# Sheet3.net
KiCad netlist of a schematic drawn in Altium Designer
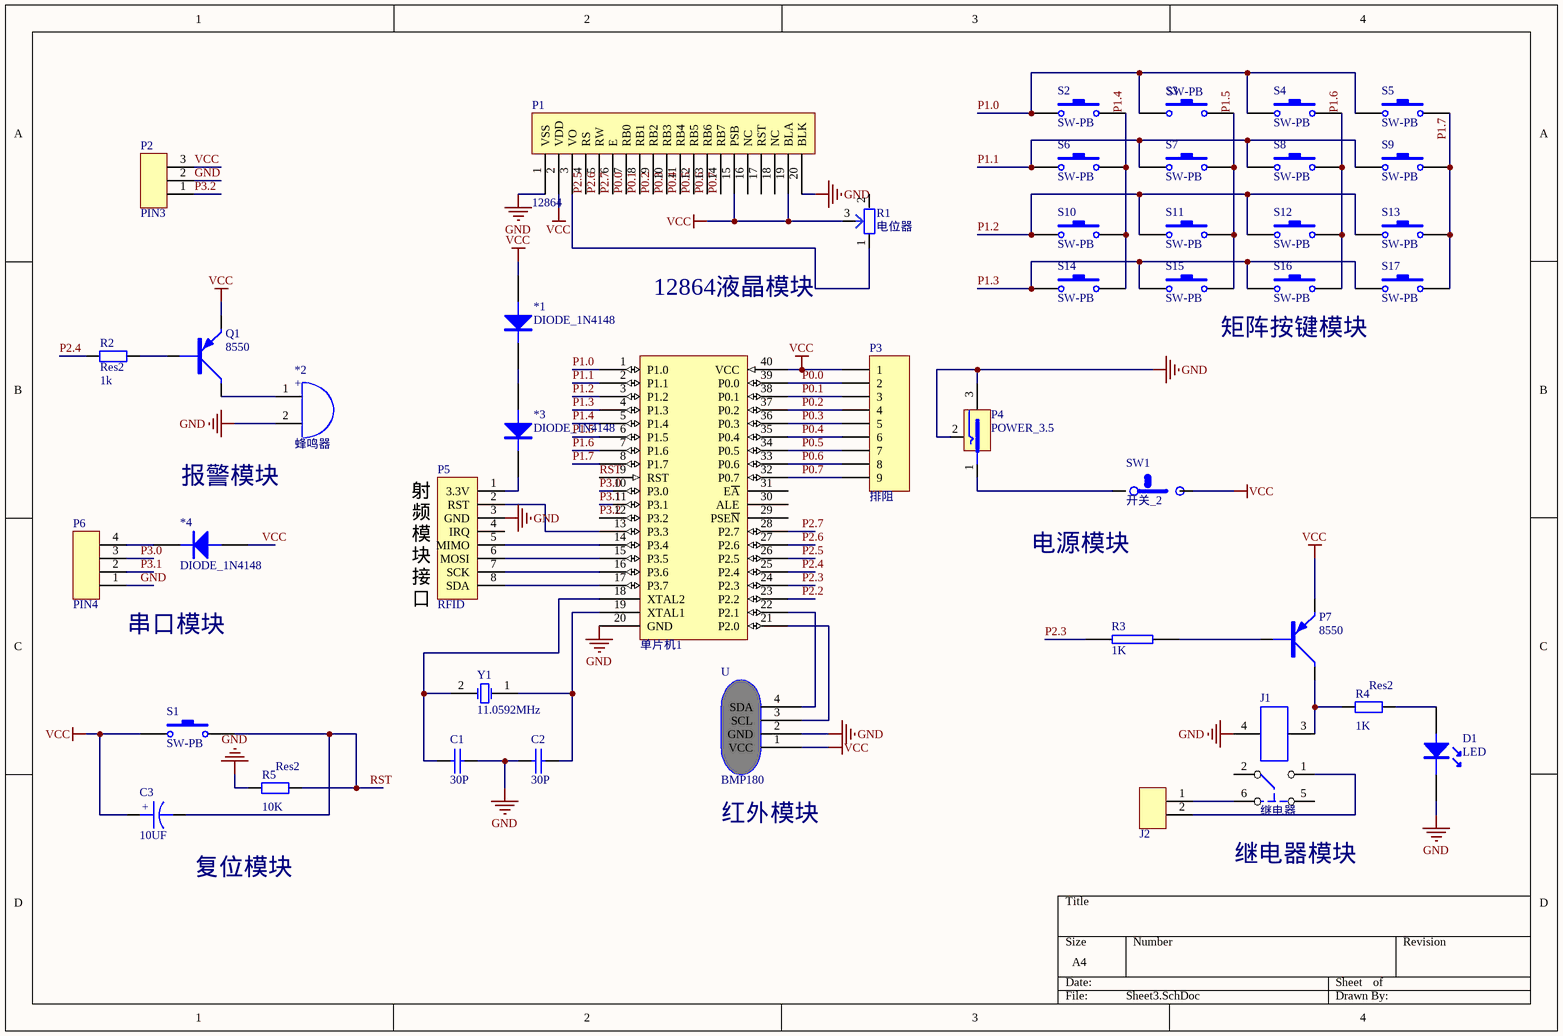
[diagram p0: Sheet3.SchDoc]

(export (version "E")
  (design (tool "Eeschema 10.0.6"))
  (components
    (comp (ref "*1")
      (value "DIODE_1N4148")
      (footprint "1N4148")
      (libsource (lib "原理图库") (part "DIODE_1N4148"))
    )
    (comp (ref "*2") (value "蜂鸣器") (footprint "蜂鸣器") (libsource (lib "原理图库") (part "蜂鸣器")))
    (comp (ref "*3")
      (value "DIODE_1N4148")
      (footprint "1N4148")
      (libsource (lib "原理图库") (part "DIODE_1N4148"))
    )
    (comp (ref "*4")
      (value "DIODE_1N4148")
      (footprint "1N4148")
      (libsource (lib "原理图库") (part "DIODE_1N4148"))
    )
    (comp (ref "C1") (value "30P") (footprint "CAP_1") (libsource (lib "原理图库") (part "CAP_1")))
    (comp (ref "C2") (value "30P") (footprint "CAP_1") (libsource (lib "原理图库") (part "CAP_1")))
    (comp (ref "C3") (value "10UF") (footprint "CAP_2") (libsource (lib "原理图库") (part "CAP_2")))
    (comp (ref "D1") (value "LED") (footprint "LED") (libsource (lib "51板元件库") (part "LED")))
    (comp (ref "J1") (value "继电器") (footprint "JDQ") (libsource (lib "原理图_CZQ") (part "继电器")))
    (comp (ref "J2")
      (value "CON2")
      (footprint "SIP2")
      (description "SOCKET")
      (libsource (lib "51板元件库") (part "CON2"))
    )
    (comp (ref "P1") (value "12864") (footprint "12864") (libsource (lib "原理图_CZQ") (part "12864")))
    (comp (ref "P2") (value "PIN3") (footprint "PIN3") (libsource (lib "原理图库") (part "PIN3")))
    (comp (ref "P3")
      (value "排阻")
      (footprint "HDR1X9")
      (description "Header, 9-Pin")
      (fields (field (name "PUBLISHER") "Altium Limited"))
      (libsource (lib "Miscellaneous Connectors") (part "Header 9"))
    )
    (comp (ref "P4") (value "POWER_3.5") (footprint "POWER_3.5") (libsource (lib "原理图库") (part "POWER_3.5")))
    (comp (ref "P5") (value "RFID") (footprint "RFID") (libsource (lib "原理图_CZQ") (part "RFID")))
    (comp (ref "P6") (value "PIN4") (footprint "PIN4") (libsource (lib "原理图库") (part "PIN4")))
    (comp (ref "P7") (value "8550") (footprint "PNP") (libsource (lib "原理图库") (part "PNP")))
    (comp (ref "Q1") (value "8550") (footprint "PNP") (libsource (lib "原理图库") (part "PNP")))
    (comp (ref "R1") (value "电位器") (footprint "电位器") (libsource (lib "原理图库") (part "电位器")))
    (comp (ref "R2")
      (value "Res2")
      (footprint "AXIAL-0.4")
      (description "Resistor")
      (fields (field (name "ALTIUM_VALUE") "1k") (field (name "PUBLISHER") "Altium Limited"))
      (libsource (lib "") (part "Res2_1"))
    )
    (comp (ref "R3") (value "1K") (footprint "RES") (libsource (lib "原理图库") (part "RES")))
    (comp (ref "R4")
      (value "Res2")
      (footprint "AXIAL-0.4")
      (description "Resistor")
      (fields (field (name "ALTIUM_VALUE") "1K") (field (name "PUBLISHER") "Altium Limited"))
      (libsource (lib "Miscellaneous Devices") (part "Res2"))
    )
    (comp (ref "R5")
      (value "Res2")
      (footprint "AXIAL-0.4")
      (description "Resistor")
      (fields (field (name "ALTIUM_VALUE") "10K") (field (name "PUBLISHER") "Altium Limited"))
      (libsource (lib "Miscellaneous Devices") (part "Res2"))
    )
    (comp (ref "S1")
      (value "SW-PB")
      (footprint "6X6X?")
      (description "Switch")
      (fields (field (name "PUBLISHER") "Altium Limited"))
      (libsource (lib "51板元件库") (part "SW-PB"))
    )
    (comp (ref "S2")
      (value "SW-PB")
      (footprint "6X6X?")
      (description "Switch")
      (fields (field (name "PUBLISHER") "Altium Limited"))
      (libsource (lib "51板元件库") (part "SW-PB"))
    )
    (comp (ref "S3")
      (value "SW-PB")
      (footprint "6X6X?")
      (description "Switch")
      (fields (field (name "PUBLISHER") "Altium Limited"))
      (libsource (lib "51板元件库") (part "SW-PB"))
    )
    (comp (ref "S4")
      (value "SW-PB")
      (footprint "6X6X?")
      (description "Switch")
      (fields (field (name "PUBLISHER") "Altium Limited"))
      (libsource (lib "51板元件库") (part "SW-PB"))
    )
    (comp (ref "S5")
      (value "SW-PB")
      (footprint "6X6X?")
      (description "Switch")
      (fields (field (name "PUBLISHER") "Altium Limited"))
      (libsource (lib "51板元件库") (part "SW-PB"))
    )
    (comp (ref "S6")
      (value "SW-PB")
      (footprint "6X6X?")
      (description "Switch")
      (fields (field (name "PUBLISHER") "Altium Limited"))
      (libsource (lib "51板元件库") (part "SW-PB"))
    )
    (comp (ref "S7")
      (value "SW-PB")
      (footprint "6X6X?")
      (description "Switch")
      (fields (field (name "PUBLISHER") "Altium Limited"))
      (libsource (lib "51板元件库") (part "SW-PB"))
    )
    (comp (ref "S8")
      (value "SW-PB")
      (footprint "6X6X?")
      (description "Switch")
      (fields (field (name "PUBLISHER") "Altium Limited"))
      (libsource (lib "51板元件库") (part "SW-PB"))
    )
    (comp (ref "S9")
      (value "SW-PB")
      (footprint "6X6X?")
      (description "Switch")
      (fields (field (name "PUBLISHER") "Altium Limited"))
      (libsource (lib "51板元件库") (part "SW-PB"))
    )
    (comp (ref "S10")
      (value "SW-PB")
      (footprint "6X6X?")
      (description "Switch")
      (fields (field (name "PUBLISHER") "Altium Limited"))
      (libsource (lib "51板元件库") (part "SW-PB"))
    )
    (comp (ref "S11")
      (value "SW-PB")
      (footprint "6X6X?")
      (description "Switch")
      (fields (field (name "PUBLISHER") "Altium Limited"))
      (libsource (lib "51板元件库") (part "SW-PB"))
    )
    (comp (ref "S12")
      (value "SW-PB")
      (footprint "6X6X?")
      (description "Switch")
      (fields (field (name "PUBLISHER") "Altium Limited"))
      (libsource (lib "51板元件库") (part "SW-PB"))
    )
    (comp (ref "S13")
      (value "SW-PB")
      (footprint "6X6X?")
      (description "Switch")
      (fields (field (name "PUBLISHER") "Altium Limited"))
      (libsource (lib "51板元件库") (part "SW-PB"))
    )
    (comp (ref "S14")
      (value "SW-PB")
      (footprint "6X6X?")
      (description "Switch")
      (fields (field (name "PUBLISHER") "Altium Limited"))
      (libsource (lib "51板元件库") (part "SW-PB"))
    )
    (comp (ref "S15")
      (value "SW-PB")
      (footprint "6X6X?")
      (description "Switch")
      (fields (field (name "PUBLISHER") "Altium Limited"))
      (libsource (lib "51板元件库") (part "SW-PB"))
    )
    (comp (ref "S16")
      (value "SW-PB")
      (footprint "6X6X?")
      (description "Switch")
      (fields (field (name "PUBLISHER") "Altium Limited"))
      (libsource (lib "51板元件库") (part "SW-PB"))
    )
    (comp (ref "S17")
      (value "SW-PB")
      (footprint "6X6X?")
      (description "Switch")
      (fields (field (name "PUBLISHER") "Altium Limited"))
      (libsource (lib "51板元件库") (part "SW-PB"))
    )
    (comp (ref "SW1") (value "开关_2") (footprint "开关_2") (libsource (lib "原理图库") (part "开关_2")))
    (comp (ref "U") (value "BMP180") (footprint "BMP180") (libsource (lib "原理图库") (part "BMP180")))
    (comp (ref "Y1")
      (value "11.0592MHz")
      (footprint "晶振")
      (description "Crystal Oscillator")
      (fields (field (name "PUBLISHER") "Altium Limited"))
      (libsource (lib "51板元件库") (part "XTAL"))
    )
    (comp (ref "单片机1") (value "AT89S52") (footprint "DIP40C") (libsource (lib "51板元件库") (part "AT89S52")))
  )
  (nets
    (net (code "1") (name "/P0.0") (class "Default")
      (node (ref "P1") (pin "7") (pinfunction "RB0_7") (pintype "passive"))
      (node (ref "P3") (pin "2") (pinfunction "2_2") (pintype "passive"))
      (node (ref "单片机1") (pin "39") (pinfunction "P0.0_39") (pintype "bidirectional"))
    )
    (net (code "2") (name "/P0.1") (class "Default")
      (node (ref "P1") (pin "8") (pinfunction "RB1_8") (pintype "passive"))
      (node (ref "P3") (pin "3") (pinfunction "3_3") (pintype "passive"))
      (node (ref "单片机1") (pin "38") (pinfunction "P0.1_38") (pintype "bidirectional"))
    )
    (net (code "3") (name "/P0.2") (class "Default")
      (node (ref "P1") (pin "9") (pinfunction "RB2_9") (pintype "passive"))
      (node (ref "P3") (pin "4") (pinfunction "4_4") (pintype "passive"))
      (node (ref "单片机1") (pin "37") (pinfunction "P0.2_37") (pintype "bidirectional"))
    )
    (net (code "4") (name "/P0.3") (class "Default")
      (node (ref "P1") (pin "10") (pinfunction "RB3_10") (pintype "passive"))
      (node (ref "P3") (pin "5") (pinfunction "5_5") (pintype "passive"))
      (node (ref "单片机1") (pin "36") (pinfunction "P0.3_36") (pintype "bidirectional"))
    )
    (net (code "5") (name "/P0.4") (class "Default")
      (node (ref "P1") (pin "11") (pinfunction "RB4_11") (pintype "passive"))
      (node (ref "P3") (pin "6") (pinfunction "6_6") (pintype "passive"))
      (node (ref "单片机1") (pin "35") (pinfunction "P0.4_35") (pintype "bidirectional"))
    )
    (net (code "6") (name "/P0.5") (class "Default")
      (node (ref "P1") (pin "12") (pinfunction "RB5_12") (pintype "passive"))
      (node (ref "P3") (pin "7") (pinfunction "7_7") (pintype "passive"))
      (node (ref "单片机1") (pin "34") (pinfunction "P0.5_34") (pintype "bidirectional"))
    )
    (net (code "7") (name "/P0.6") (class "Default")
      (node (ref "P1") (pin "13") (pinfunction "RB6_13") (pintype "passive"))
      (node (ref "P3") (pin "8") (pinfunction "8_8") (pintype "passive"))
      (node (ref "单片机1") (pin "33") (pinfunction "P0.6_33") (pintype "bidirectional"))
    )
    (net (code "8") (name "/P0.7") (class "Default")
      (node (ref "P1") (pin "14") (pinfunction "RB7_14") (pintype "passive"))
      (node (ref "P3") (pin "9") (pinfunction "9_9") (pintype "passive"))
      (node (ref "单片机1") (pin "32") (pinfunction "P0.7_32") (pintype "bidirectional"))
    )
    (net (code "9") (name "/P1.0") (class "Default")
      (node (ref "S2") (pin "1") (pinfunction "1_1") (pintype "passive"))
      (node (ref "S3") (pin "1") (pinfunction "1_1") (pintype "passive"))
      (node (ref "S4") (pin "1") (pinfunction "1_1") (pintype "passive"))
      (node (ref "S5") (pin "1") (pinfunction "1_1") (pintype "passive"))
      (node (ref "单片机1") (pin "1") (pinfunction "P1.0_1") (pintype "bidirectional"))
    )
    (net (code "10") (name "/P1.1") (class "Default")
      (node (ref "S6") (pin "1") (pinfunction "1_1") (pintype "passive"))
      (node (ref "S7") (pin "1") (pinfunction "1_1") (pintype "passive"))
      (node (ref "S8") (pin "1") (pinfunction "1_1") (pintype "passive"))
      (node (ref "S9") (pin "1") (pinfunction "1_1") (pintype "passive"))
      (node (ref "单片机1") (pin "2") (pinfunction "P1.1_2") (pintype "bidirectional"))
    )
    (net (code "11") (name "/P1.2") (class "Default")
      (node (ref "S10") (pin "1") (pinfunction "1_1") (pintype "passive"))
      (node (ref "S11") (pin "1") (pinfunction "1_1") (pintype "passive"))
      (node (ref "S12") (pin "1") (pinfunction "1_1") (pintype "passive"))
      (node (ref "S13") (pin "1") (pinfunction "1_1") (pintype "passive"))
      (node (ref "单片机1") (pin "3") (pinfunction "P1.2_3") (pintype "bidirectional"))
    )
    (net (code "12") (name "/P1.3") (class "Default")
      (node (ref "S14") (pin "1") (pinfunction "1_1") (pintype "passive"))
      (node (ref "S15") (pin "1") (pinfunction "1_1") (pintype "passive"))
      (node (ref "S16") (pin "1") (pinfunction "1_1") (pintype "passive"))
      (node (ref "S17") (pin "1") (pinfunction "1_1") (pintype "passive"))
      (node (ref "单片机1") (pin "4") (pinfunction "P1.3_4") (pintype "bidirectional"))
    )
    (net (code "13") (name "/P1.4") (class "Default")
      (node (ref "S10") (pin "2") (pinfunction "2_2") (pintype "passive"))
      (node (ref "S14") (pin "2") (pinfunction "2_2") (pintype "passive"))
      (node (ref "S2") (pin "2") (pinfunction "2_2") (pintype "passive"))
      (node (ref "S6") (pin "2") (pinfunction "2_2") (pintype "passive"))
      (node (ref "单片机1") (pin "5") (pinfunction "P1.4_5") (pintype "bidirectional"))
    )
    (net (code "14") (name "/P1.5") (class "Default")
      (node (ref "S11") (pin "2") (pinfunction "2_2") (pintype "passive"))
      (node (ref "S15") (pin "2") (pinfunction "2_2") (pintype "passive"))
      (node (ref "S3") (pin "2") (pinfunction "2_2") (pintype "passive"))
      (node (ref "S7") (pin "2") (pinfunction "2_2") (pintype "passive"))
      (node (ref "单片机1") (pin "6") (pinfunction "P1.5_6") (pintype "bidirectional"))
    )
    (net (code "15") (name "/P1.6") (class "Default")
      (node (ref "S12") (pin "2") (pinfunction "2_2") (pintype "passive"))
      (node (ref "S16") (pin "2") (pinfunction "2_2") (pintype "passive"))
      (node (ref "S4") (pin "2") (pinfunction "2_2") (pintype "passive"))
      (node (ref "S8") (pin "2") (pinfunction "2_2") (pintype "passive"))
      (node (ref "单片机1") (pin "7") (pinfunction "P1.6_7") (pintype "bidirectional"))
    )
    (net (code "16") (name "/P1.7") (class "Default")
      (node (ref "S13") (pin "2") (pinfunction "2_2") (pintype "passive"))
      (node (ref "S17") (pin "2") (pinfunction "2_2") (pintype "passive"))
      (node (ref "S5") (pin "2") (pinfunction "2_2") (pintype "passive"))
      (node (ref "S9") (pin "2") (pinfunction "2_2") (pintype "passive"))
      (node (ref "单片机1") (pin "8") (pinfunction "P1.7_8") (pintype "bidirectional"))
    )
    (net (code "17") (name "/P2.2") (class "Default")
      (node (ref "单片机1") (pin "23") (pinfunction "P2.2_23") (pintype "bidirectional"))
    )
    (net (code "18") (name "/P2.3") (class "Default")
      (node (ref "R3") (pin "1") (pinfunction "1_1") (pintype "passive"))
      (node (ref "单片机1") (pin "24") (pinfunction "P2.3_24") (pintype "bidirectional"))
    )
    (net (code "19") (name "/P2.4") (class "Default")
      (node (ref "R2") (pin "2") (pinfunction "2_2") (pintype "passive"))
      (node (ref "单片机1") (pin "25") (pinfunction "P2.4_25") (pintype "bidirectional"))
    )
    (net (code "20") (name "/P2.5") (class "Default")
      (node (ref "P1") (pin "4") (pinfunction "RS_4") (pintype "passive"))
      (node (ref "单片机1") (pin "26") (pinfunction "P2.5_26") (pintype "bidirectional"))
    )
    (net (code "21") (name "/P2.6") (class "Default")
      (node (ref "P1") (pin "5") (pinfunction "RW_5") (pintype "passive"))
      (node (ref "单片机1") (pin "27") (pinfunction "P2.6_27") (pintype "bidirectional"))
    )
    (net (code "22") (name "/P2.7") (class "Default")
      (node (ref "P1") (pin "6") (pinfunction "E_6") (pintype "passive"))
      (node (ref "单片机1") (pin "28") (pinfunction "P2.7_28") (pintype "bidirectional"))
    )
    (net (code "23") (name "/P3.0") (class "Default")
      (node (ref "P6") (pin "3") (pintype "passive"))
      (node (ref "单片机1") (pin "10") (pinfunction "P3.0_10") (pintype "bidirectional"))
    )
    (net (code "24") (name "/P3.1") (class "Default")
      (node (ref "P6") (pin "2") (pintype "passive"))
      (node (ref "单片机1") (pin "11") (pinfunction "P3.1_11") (pintype "bidirectional"))
    )
    (net (code "25") (name "/P3.2") (class "Default")
      (node (ref "P2") (pin "1") (pintype "passive"))
      (node (ref "单片机1") (pin "12") (pinfunction "P3.2_12") (pintype "bidirectional"))
    )
    (net (code "26") (name "/RST") (class "Default")
      (node (ref "C3") (pin "2") (pinfunction "2_2") (pintype "passive"))
      (node (ref "R5") (pin "2") (pinfunction "2_2") (pintype "passive"))
      (node (ref "S1") (pin "2") (pinfunction "2_2") (pintype "passive"))
      (node (ref "单片机1") (pin "9") (pinfunction "RST_9") (pintype "input"))
    )
    (net (code "27") (name "GND") (class "Default")
      (node (ref "*2") (pin "2") (pinfunction "1_2") (pintype "passive"))
      (node (ref "C1") (pin "2") (pinfunction "2_2") (pintype "passive"))
      (node (ref "C2") (pin "1") (pinfunction "1_1") (pintype "passive"))
      (node (ref "D1") (pin "2") (pinfunction "2_2") (pintype "passive"))
      (node (ref "J1") (pin "4") (pinfunction "4_4") (pintype "passive"))
      (node (ref "P1") (pin "1") (pinfunction "VSS_1") (pintype "passive"))
      (node (ref "P1") (pin "20") (pinfunction "BLK_20") (pintype "passive"))
      (node (ref "P2") (pin "2") (pintype "passive"))
      (node (ref "P4") (pin "2") (pintype "passive"))
      (node (ref "P4") (pin "3") (pintype "passive"))
      (node (ref "P5") (pin "3") (pinfunction "GND_3") (pintype "passive"))
      (node (ref "P6") (pin "1") (pintype "passive"))
      (node (ref "R5") (pin "1") (pinfunction "1_1") (pintype "passive"))
      (node (ref "U") (pin "2") (pinfunction "GND_2") (pintype "passive"))
      (node (ref "单片机1") (pin "20") (pinfunction "GND_20") (pintype "passive"))
    )
    (net (code "28") (name "Net-(*1-PadK)") (class "Default")
      (node (ref "*1") (pin "K") (pinfunction "K_K") (pintype "passive"))
      (node (ref "*3") (pin "A") (pinfunction "A_A") (pintype "passive"))
    )
    (net (code "29") (name "Net-(*2-2)") (class "Default")
      (node (ref "*2") (pin "1") (pinfunction "2_1") (pintype "passive"))
      (node (ref "Q1") (pin "3") (pinfunction "C_3") (pintype "passive"))
    )
    (net (code "30") (name "Net-(*4-PadK)") (class "Default")
      (node (ref "*4") (pin "K") (pinfunction "K_K") (pintype "passive"))
      (node (ref "P6") (pin "4") (pinfunction "4_4") (pintype "passive"))
    )
    (net (code "31") (name "Net-(D1-Pad1)") (class "Default")
      (node (ref "D1") (pin "1") (pinfunction "1_1") (pintype "passive"))
      (node (ref "R4") (pin "2") (pinfunction "2_2") (pintype "passive"))
    )
    (net (code "32") (name "Net-(J1-Pad1)") (class "Default")
      (node (ref "J1") (pin "1") (pinfunction "1_1") (pintype "passive"))
      (node (ref "J2") (pin "2") (pinfunction "2_2") (pintype "passive"))
    )
    (net (code "33") (name "Net-(J1-Pad6)") (class "Default")
      (node (ref "J1") (pin "6") (pinfunction "6_6") (pintype "passive"))
      (node (ref "J2") (pin "1") (pinfunction "1_1") (pintype "passive"))
    )
    (net (code "34") (name "Net-(P1-VO)") (class "Default")
      (node (ref "P1") (pin "3") (pinfunction "VO_3") (pintype "passive"))
      (node (ref "R1") (pin "1") (pinfunction "1_1") (pintype "passive"))
    )
    (net (code "35") (name "Net-(P4-Pad1)") (class "Default")
      (node (ref "P4") (pin "1") (pintype "passive"))
      (node (ref "SW1") (pin "1") (pinfunction "1_1") (pintype "passive"))
    )
    (net (code "36") (name "Net-(P5-3.3V)") (class "Default")
      (node (ref "*3") (pin "K") (pinfunction "K_K") (pintype "passive"))
      (node (ref "P5") (pin "1") (pinfunction "3.3V_1") (pintype "passive"))
    )
    (net (code "37") (name "Net-(P5-MIMO)") (class "Default")
      (node (ref "P5") (pin "5") (pinfunction "MIMO_5") (pintype "passive"))
      (node (ref "单片机1") (pin "14") (pinfunction "P3.4_14") (pintype "bidirectional"))
    )
    (net (code "38") (name "Net-(P5-MOSI)") (class "Default")
      (node (ref "P5") (pin "6") (pinfunction "MOSI_6") (pintype "passive"))
      (node (ref "单片机1") (pin "15") (pinfunction "P3.5_15") (pintype "bidirectional"))
    )
    (net (code "39") (name "Net-(P5-RST)") (class "Default")
      (node (ref "P5") (pin "2") (pinfunction "RST_2") (pintype "passive"))
      (node (ref "单片机1") (pin "13") (pinfunction "P3.3_13") (pintype "bidirectional"))
    )
    (net (code "40") (name "Net-(P5-SCK)") (class "Default")
      (node (ref "P5") (pin "7") (pinfunction "SCK_7") (pintype "passive"))
      (node (ref "单片机1") (pin "16") (pinfunction "P3.6_16") (pintype "bidirectional"))
    )
    (net (code "41") (name "Net-(P5-SDA)") (class "Default")
      (node (ref "P5") (pin "8") (pinfunction "SDA_8") (pintype "passive"))
      (node (ref "单片机1") (pin "17") (pinfunction "P3.7_17") (pintype "bidirectional"))
    )
    (net (code "42") (name "Net-(P7-B)") (class "Default")
      (node (ref "P7") (pin "2") (pinfunction "B_2") (pintype "passive"))
      (node (ref "R3") (pin "2") (pinfunction "2_2") (pintype "passive"))
    )
    (net (code "43") (name "Net-(P7-C)") (class "Default")
      (node (ref "J1") (pin "3") (pinfunction "3_3") (pintype "passive"))
      (node (ref "P7") (pin "3") (pinfunction "C_3") (pintype "passive"))
      (node (ref "R4") (pin "1") (pinfunction "1_1") (pintype "passive"))
    )
    (net (code "44") (name "Net-(Q1-B)") (class "Default")
      (node (ref "Q1") (pin "2") (pinfunction "B_2") (pintype "passive"))
      (node (ref "R2") (pin "1") (pinfunction "1_1") (pintype "passive"))
    )
    (net (code "45") (name "Net-(U-SCL)") (class "Default")
      (node (ref "U") (pin "3") (pinfunction "SCL_3") (pintype "passive"))
      (node (ref "单片机1") (pin "21") (pinfunction "P2.0_21") (pintype "bidirectional"))
    )
    (net (code "46") (name "Net-(U-SDA)") (class "Default")
      (node (ref "U") (pin "4") (pinfunction "SDA_4") (pintype "passive"))
      (node (ref "单片机1") (pin "22") (pinfunction "P2.1_22") (pintype "bidirectional"))
    )
    (net (code "47") (name "Net-(Y1-OSC1)") (class "Default")
      (node (ref "C2") (pin "2") (pinfunction "2_2") (pintype "passive"))
      (node (ref "Y1") (pin "1") (pinfunction "OSC1_1") (pintype "passive"))
      (node (ref "单片机1") (pin "19") (pinfunction "XTAL1_19") (pintype "passive"))
    )
    (net (code "48") (name "Net-(Y1-OSC2)") (class "Default")
      (node (ref "C1") (pin "1") (pinfunction "1_1") (pintype "passive"))
      (node (ref "Y1") (pin "2") (pinfunction "OSC2_2") (pintype "passive"))
      (node (ref "单片机1") (pin "18") (pinfunction "XTAL2_18") (pintype "passive"))
    )
    (net (code "49") (name "VCC") (class "Default")
      (node (ref "*1") (pin "A") (pinfunction "A_A") (pintype "passive"))
      (node (ref "*4") (pin "A") (pinfunction "A_A") (pintype "passive"))
      (node (ref "C3") (pin "1") (pinfunction "1_1") (pintype "passive"))
      (node (ref "P1") (pin "15") (pinfunction "PSB_15") (pintype "passive"))
      (node (ref "P1") (pin "19") (pinfunction "BLA_19") (pintype "passive"))
      (node (ref "P1") (pin "2") (pinfunction "VDD_2") (pintype "passive"))
      (node (ref "P2") (pin "3") (pintype "passive"))
      (node (ref "P3") (pin "1") (pinfunction "1_1") (pintype "passive"))
      (node (ref "P7") (pin "1") (pinfunction "E_1") (pintype "passive"))
      (node (ref "Q1") (pin "1") (pinfunction "E_1") (pintype "passive"))
      (node (ref "R1") (pin "3") (pinfunction "3_3") (pintype "passive"))
      (node (ref "S1") (pin "1") (pinfunction "1_1") (pintype "passive"))
      (node (ref "SW1") (pin "2") (pinfunction "2_2") (pintype "passive"))
      (node (ref "U") (pin "1") (pinfunction "VCC_1") (pintype "passive"))
      (node (ref "单片机1") (pin "40") (pinfunction "VCC_40") (pintype "input"))
    )
    (net (code "50") (name "unconnected-(J1-Pad2)") (class "Default")
      (node (ref "J1") (pin "2") (pinfunction "2_2") (pintype "passive"))
    )
    (net (code "51") (name "unconnected-(J1-Pad5)") (class "Default")
      (node (ref "J1") (pin "5") (pinfunction "5_5") (pintype "passive"))
    )
    (net (code "52") (name "unconnected-(P1-NC-Pad16)") (class "Default")
      (node (ref "P1") (pin "16") (pinfunction "NC_16") (pintype "passive"))
    )
    (net (code "53") (name "unconnected-(P1-NC-Pad18)") (class "Default")
      (node (ref "P1") (pin "18") (pinfunction "NC_18") (pintype "passive"))
    )
    (net (code "54") (name "unconnected-(P1-RST-Pad17)") (class "Default")
      (node (ref "P1") (pin "17") (pinfunction "RST_17") (pintype "passive"))
    )
    (net (code "55") (name "unconnected-(P5-IRQ-Pad4)") (class "Default")
      (node (ref "P5") (pin "4") (pinfunction "IRQ_4") (pintype "passive"))
    )
    (net (code "56") (name "unconnected-(R1-Pad2)") (class "Default")
      (node (ref "R1") (pin "2") (pinfunction "2_2") (pintype "passive"))
    )
    (net (code "57") (name "unconnected-(单片机1-ALE-Pad30)") (class "Default")
      (node (ref "单片机1") (pin "30") (pinfunction "ALE_30") (pintype "passive"))
    )
    (net (code "58") (name "unconnected-(单片机1-E~{A}-Pad31)") (class "Default")
      (node (ref "单片机1") (pin "31") (pinfunction "E~{A}_31") (pintype "passive"))
    )
    (net (code "59") (name "unconnected-(单片机1-PSE~{N}-Pad29)") (class "Default")
      (node (ref "单片机1") (pin "29") (pinfunction "PSE~{N}_29") (pintype "passive"))
    )
  )
)
